# 000_Main.net
KiCad netlist of a schematic drawn in Altium Designer
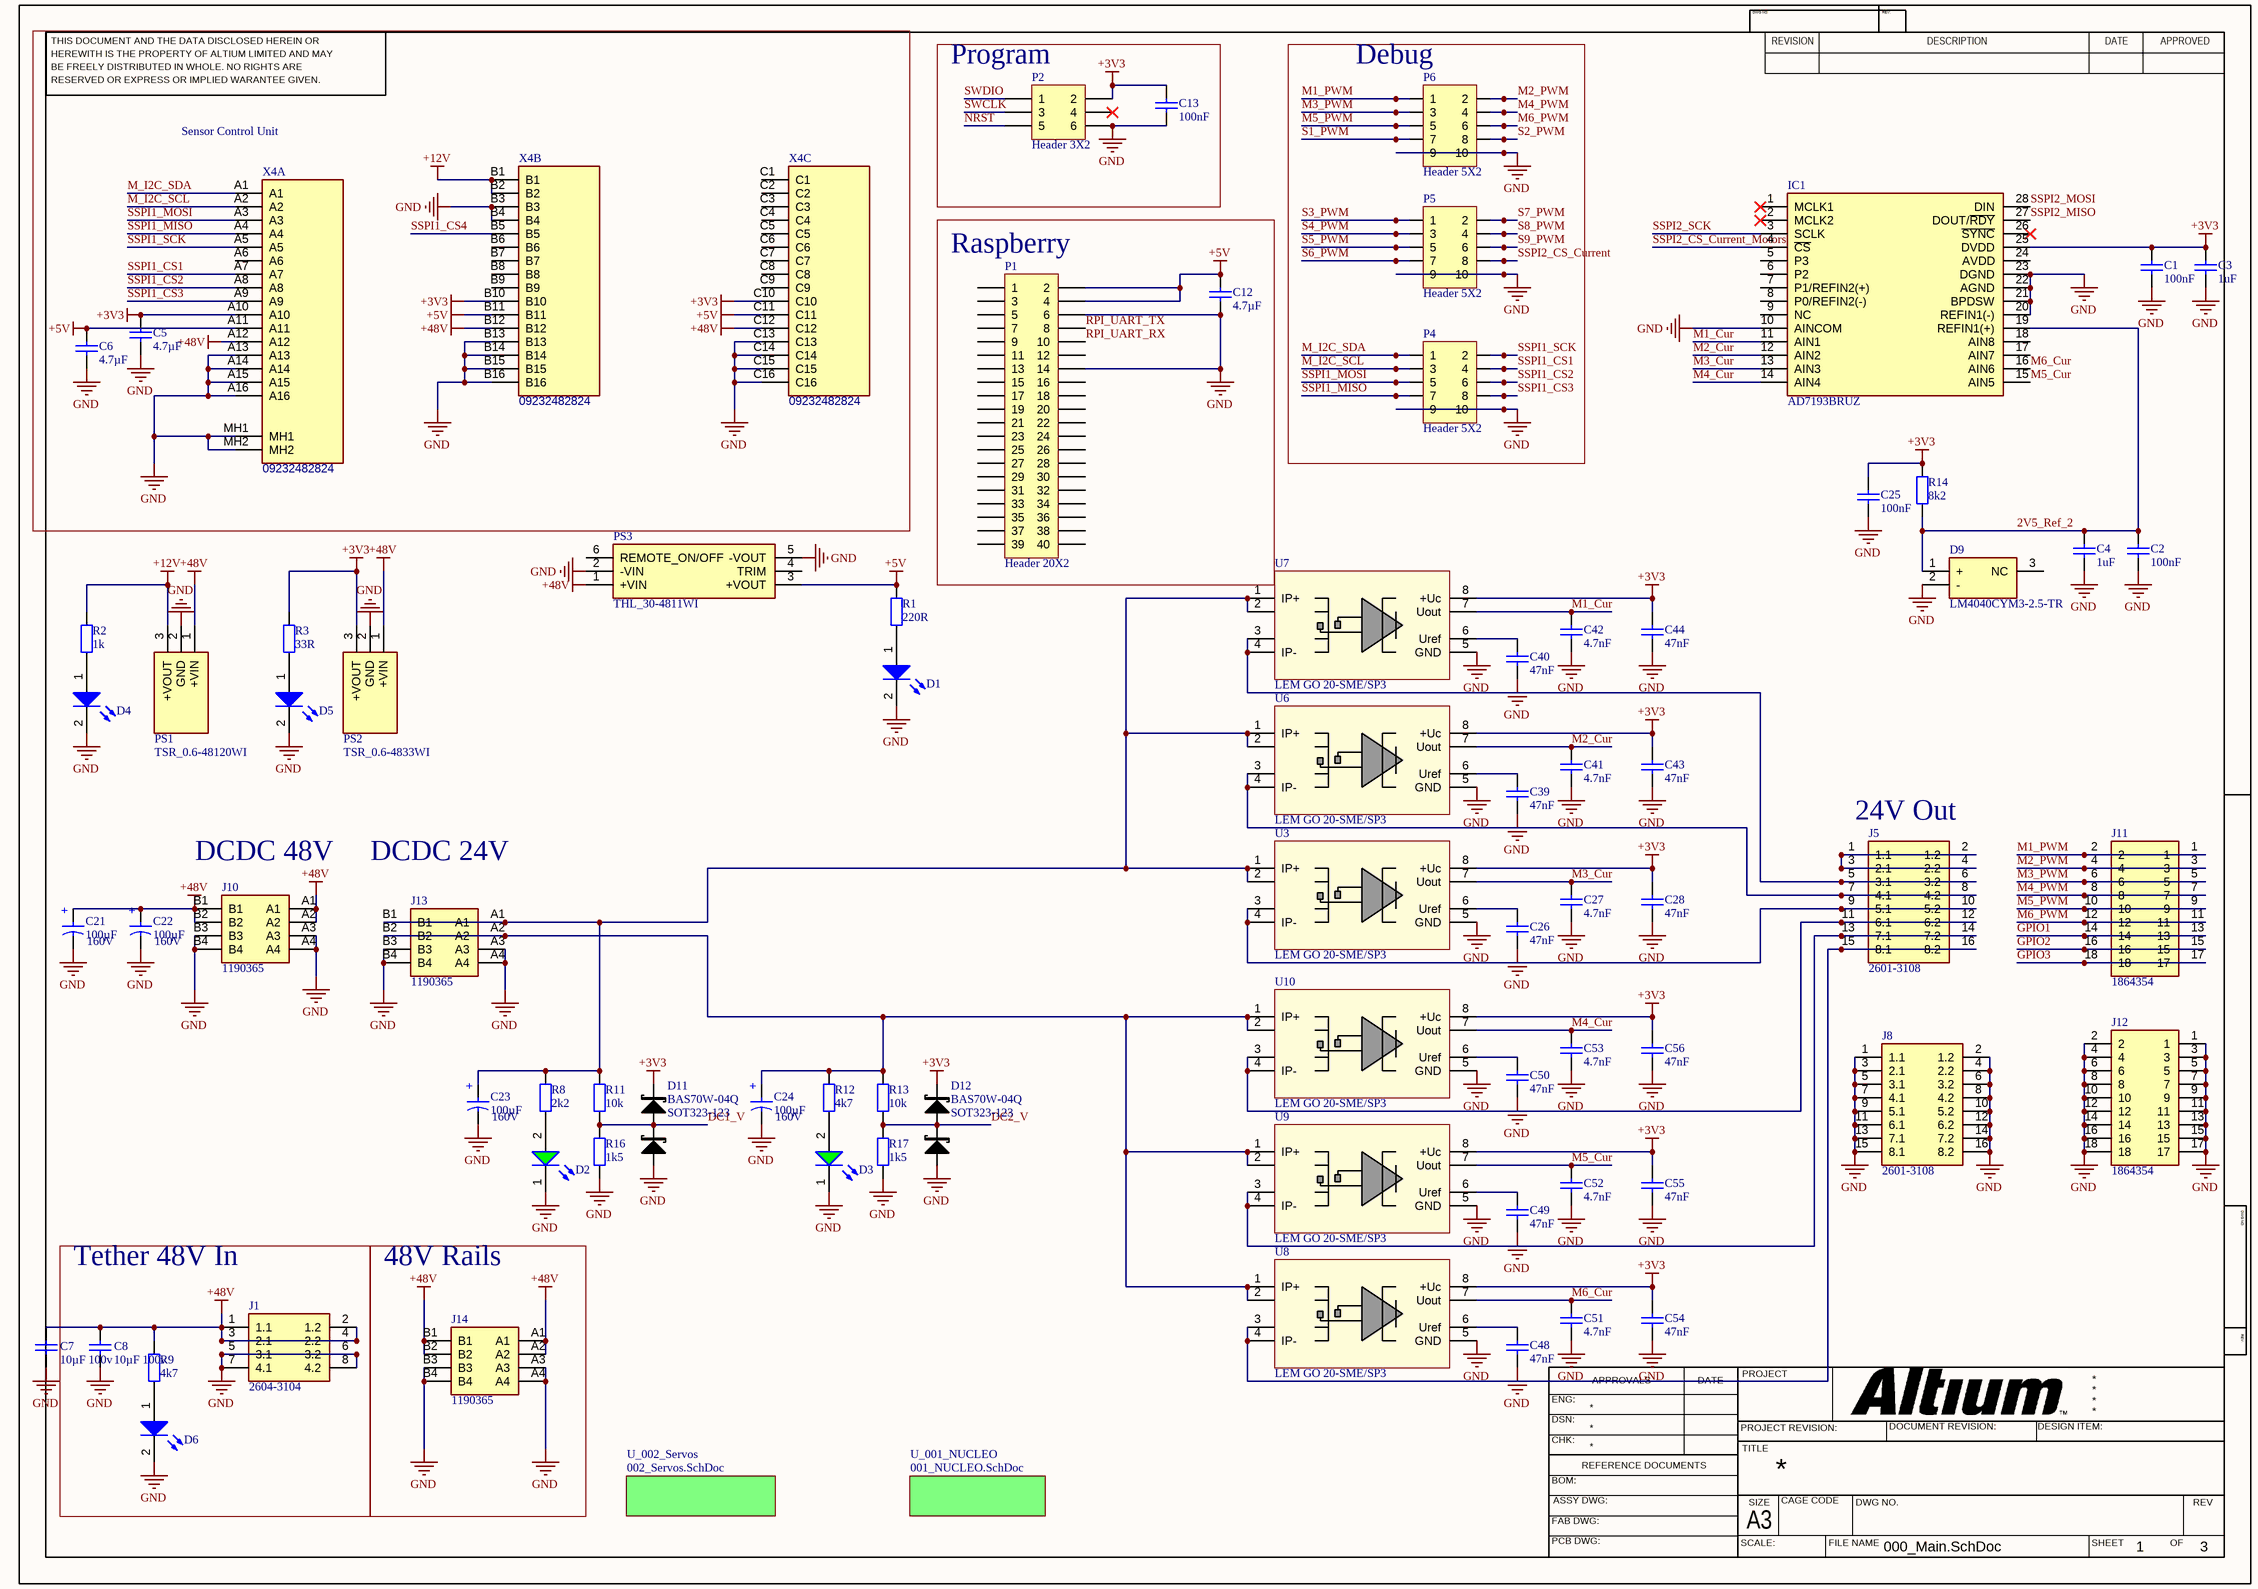
[diagram p0: 000_Main.SchDoc]

(export (version "E")
  (design (tool "Eeschema 10.0.6"))
  (components
    (comp (ref "C1")
      (value "100nF")
      (footprint "Miscellaneous Devices:6-0805_L")
      (description "Capacitor")
      (fields (field (name "PUBLISHER") "Altium Limited"))
      (libsource (lib "Miscellaneous Devices") (part "Cap"))
    )
    (comp (ref "C2")
      (value "100nF")
      (footprint "Miscellaneous Devices:6-0805_L")
      (description "Capacitor")
      (fields (field (name "PUBLISHER") "Altium Limited"))
      (libsource (lib "Miscellaneous Devices") (part "Cap"))
    )
    (comp (ref "C3")
      (value "1uF")
      (footprint "Miscellaneous Devices:6-0805_L")
      (description "Capacitor")
      (fields (field (name "PUBLISHER") "Altium Limited"))
      (libsource (lib "Miscellaneous Devices") (part "Cap"))
    )
    (comp (ref "C4")
      (value "1uF")
      (footprint "Miscellaneous Devices:6-0805_L")
      (description "Capacitor")
      (fields (field (name "PUBLISHER") "Altium Limited"))
      (libsource (lib "Miscellaneous Devices") (part "Cap"))
    )
    (comp (ref "C5")
      (value "4.7µF")
      (footprint "WCAP-CSGP_1210_L3.2W2.5H2.5")
      (description "WCAP-CSGP Multilayer Ceramic Chip Capacitor, General Purpose, size 1210, X7R, 4.7µF, 50VDC")
      (fields
        (field (name "MANUFACTURER PART NUMBER") "885012209048")
        (field (name "MANUFACTURER") "Wurth Elektronik")
      )
      (libsource (lib "Altium_WCAP-CSGP (rev22f)") (part "885012209048"))
    )
    (comp (ref "C6")
      (value "4.7µF")
      (footprint "WCAP-CSGP_1210_L3.2W2.5H2.5")
      (description "WCAP-CSGP Multilayer Ceramic Chip Capacitor, General Purpose, size 1210, X7R, 4.7µF, 50VDC")
      (fields
        (field (name "MANUFACTURER PART NUMBER") "885012209048")
        (field (name "MANUFACTURER") "Wurth Elektronik")
      )
      (libsource (lib "Altium_WCAP-CSGP (rev22f)") (part "885012209048"))
    )
    (comp (ref "C7")
      (value "10µF 100v")
      (footprint "WCAP-CSGP_2220_L5.7W5H2.8")
      (fields
        (field (name "MANUFACTURER PART NUMBER") "885012214006")
        (field (name "MANUFACTURER") "Wurth Elektronik")
      )
      (libsource (lib "Altium_WCAP-CSGP (rev22f)") (part "885012214006"))
    )
    (comp (ref "C8")
      (value "10µF 100v")
      (footprint "WCAP-CSGP_2220_L5.7W5H2.8")
      (fields
        (field (name "MANUFACTURER PART NUMBER") "885012214006")
        (field (name "MANUFACTURER") "Wurth Elektronik")
      )
      (libsource (lib "Altium_WCAP-CSGP (rev22f)") (part "885012214006"))
    )
    (comp (ref "C12")
      (value "4.7µF")
      (footprint "WCAP-CSGP_1210_L3.2W2.5H2.5")
      (description "WCAP-CSGP Multilayer Ceramic Chip Capacitor, General Purpose, size 1210, X7R, 4.7µF, 50VDC")
      (fields
        (field (name "MANUFACTURER PART NUMBER") "885012209048")
        (field (name "MANUFACTURER") "Wurth Elektronik")
      )
      (libsource (lib "Altium_WCAP-CSGP (rev22f)") (part "885012209048"))
    )
    (comp (ref "C13")
      (value "100nF")
      (footprint "WCAP-CSGP_0805_L2W1.25H0.8_Reflow")
      (description "WCAP-CSGP Multilayer Ceramic Chip Capacitor, General Purpose, size 0805, X7R, 100nF, 50VDC")
      (fields
        (field (name "MANUFACTURER PART NUMBER") "885012207098R")
        (field (name "MANUFACTURER") "Wurth Elektronik")
      )
      (libsource (lib "Altium_WCAP-CSGP (rev22f)") (part "885012207098R"))
    )
    (comp (ref "C21")
      (value "100µF")
      (footprint "WCAP-AT1H_D18H21")
      (description "WCAP-AT1H Aluminum Electrolytic Capacitor, Radial, THT, D18 x H21mm, 100µF, 160V")
      (fields
        (field (name "MANUFACTURER PART NUMBER") "860240981006")
        (field (name "MANUFACTURER") "Wurth Elektronik")
        (field (name "CAPACITANCE") "100µF")
        (field (name "RATED VOLTAGE (DC)") "160V")
      )
      (libsource (lib "Altium_WCAP-AT1H (rev22c)") (part "860240981006"))
    )
    (comp (ref "C22")
      (value "100µF")
      (footprint "WCAP-AT1H_D18H21")
      (description "WCAP-AT1H Aluminum Electrolytic Capacitor, Radial, THT, D18 x H21mm, 100µF, 160V")
      (fields
        (field (name "MANUFACTURER PART NUMBER") "860240981006")
        (field (name "MANUFACTURER") "Wurth Elektronik")
        (field (name "CAPACITANCE") "100µF")
        (field (name "RATED VOLTAGE (DC)") "160V")
      )
      (libsource (lib "Altium_WCAP-AT1H (rev22c)") (part "860240981006"))
    )
    (comp (ref "C23")
      (value "100µF")
      (footprint "WCAP-AT1H_D18H21")
      (description "WCAP-AT1H Aluminum Electrolytic Capacitor, Radial, THT, D18 x H21mm, 100µF, 160V")
      (fields
        (field (name "MANUFACTURER PART NUMBER") "860240981006")
        (field (name "MANUFACTURER") "Wurth Elektronik")
        (field (name "CAPACITANCE") "100µF")
        (field (name "RATED VOLTAGE (DC)") "160V")
      )
      (libsource (lib "Altium_WCAP-AT1H (rev22c)") (part "860240981006"))
    )
    (comp (ref "C24")
      (value "100µF")
      (footprint "WCAP-AT1H_D18H21")
      (description "WCAP-AT1H Aluminum Electrolytic Capacitor, Radial, THT, D18 x H21mm, 100µF, 160V")
      (fields
        (field (name "MANUFACTURER PART NUMBER") "860240981006")
        (field (name "MANUFACTURER") "Wurth Elektronik")
        (field (name "CAPACITANCE") "100µF")
        (field (name "RATED VOLTAGE (DC)") "160V")
      )
      (libsource (lib "Altium_WCAP-AT1H (rev22c)") (part "860240981006"))
    )
    (comp (ref "C25")
      (value "100nF")
      (footprint "Miscellaneous Devices:6-0805_L")
      (description "Capacitor")
      (fields (field (name "PUBLISHER") "Altium Limited"))
      (libsource (lib "Miscellaneous Devices") (part "Cap"))
    )
    (comp (ref "C26")
      (value "47nF")
      (footprint "WCAP-CSGP_0805_L2W1.25H0.8_Reflow")
      (description "WCAP-CSGP Multilayer Ceramic Chip Capacitor, General Purpose, size 0805, X7R, 47nF, 50VDC")
      (fields
        (field (name "MANUFACTURER PART NUMBER") "885012207096")
        (field (name "MANUFACTURER") "Wurth Elektronik")
        (field (name "CAPACITANCE") "47nF")
      )
      (libsource (lib "Altium_WCAP-CSGP (rev22f)") (part "885012207096"))
    )
    (comp (ref "C27")
      (value "4.7nF")
      (footprint "WCAP-CSGP_0805_L2W1.25H0.8_Reflow")
      (description "WCAP-CSGP Multilayer Ceramic Chip Capacitor, General Purpose, size 0805, X7R, 4.7nF, 50VDC")
      (fields
        (field (name "MANUFACTURER PART NUMBER") "885012207090")
        (field (name "MANUFACTURER") "Wurth Elektronik")
        (field (name "CAPACITANCE") "4.7nF")
      )
      (libsource (lib "Altium_WCAP-CSGP (rev22f)") (part "885012207090"))
    )
    (comp (ref "C28")
      (value "47nF")
      (footprint "WCAP-CSGP_0805_L2W1.25H0.8_Reflow")
      (description "WCAP-CSGP Multilayer Ceramic Chip Capacitor, General Purpose, size 0805, X7R, 47nF, 50VDC")
      (fields
        (field (name "MANUFACTURER PART NUMBER") "885012207096")
        (field (name "MANUFACTURER") "Wurth Elektronik")
        (field (name "CAPACITANCE") "47nF")
      )
      (libsource (lib "Altium_WCAP-CSGP (rev22f)") (part "885012207096"))
    )
    (comp (ref "C39")
      (value "47nF")
      (footprint "WCAP-CSGP_0805_L2W1.25H0.8_Reflow")
      (description "WCAP-CSGP Multilayer Ceramic Chip Capacitor, General Purpose, size 0805, X7R, 47nF, 50VDC")
      (fields
        (field (name "MANUFACTURER PART NUMBER") "885012207096")
        (field (name "MANUFACTURER") "Wurth Elektronik")
        (field (name "CAPACITANCE") "47nF")
      )
      (libsource (lib "Altium_WCAP-CSGP (rev22f)") (part "885012207096"))
    )
    (comp (ref "C40")
      (value "47nF")
      (footprint "WCAP-CSGP_0805_L2W1.25H0.8_Reflow")
      (description "WCAP-CSGP Multilayer Ceramic Chip Capacitor, General Purpose, size 0805, X7R, 47nF, 50VDC")
      (fields
        (field (name "MANUFACTURER PART NUMBER") "885012207096")
        (field (name "MANUFACTURER") "Wurth Elektronik")
        (field (name "CAPACITANCE") "47nF")
      )
      (libsource (lib "Altium_WCAP-CSGP (rev22f)") (part "885012207096"))
    )
    (comp (ref "C41")
      (value "4.7nF")
      (footprint "WCAP-CSGP_0805_L2W1.25H0.8_Reflow")
      (description "WCAP-CSGP Multilayer Ceramic Chip Capacitor, General Purpose, size 0805, X7R, 4.7nF, 50VDC")
      (fields
        (field (name "MANUFACTURER PART NUMBER") "885012207090")
        (field (name "MANUFACTURER") "Wurth Elektronik")
        (field (name "CAPACITANCE") "4.7nF")
      )
      (libsource (lib "Altium_WCAP-CSGP (rev22f)") (part "885012207090"))
    )
    (comp (ref "C42")
      (value "4.7nF")
      (footprint "WCAP-CSGP_0805_L2W1.25H0.8_Reflow")
      (description "WCAP-CSGP Multilayer Ceramic Chip Capacitor, General Purpose, size 0805, X7R, 4.7nF, 50VDC")
      (fields
        (field (name "MANUFACTURER PART NUMBER") "885012207090")
        (field (name "MANUFACTURER") "Wurth Elektronik")
        (field (name "CAPACITANCE") "4.7nF")
      )
      (libsource (lib "Altium_WCAP-CSGP (rev22f)") (part "885012207090"))
    )
    (comp (ref "C43")
      (value "47nF")
      (footprint "WCAP-CSGP_0805_L2W1.25H0.8_Reflow")
      (description "WCAP-CSGP Multilayer Ceramic Chip Capacitor, General Purpose, size 0805, X7R, 47nF, 50VDC")
      (fields
        (field (name "MANUFACTURER PART NUMBER") "885012207096")
        (field (name "MANUFACTURER") "Wurth Elektronik")
        (field (name "CAPACITANCE") "47nF")
      )
      (libsource (lib "Altium_WCAP-CSGP (rev22f)") (part "885012207096"))
    )
    (comp (ref "C44")
      (value "47nF")
      (footprint "WCAP-CSGP_0805_L2W1.25H0.8_Reflow")
      (description "WCAP-CSGP Multilayer Ceramic Chip Capacitor, General Purpose, size 0805, X7R, 47nF, 50VDC")
      (fields
        (field (name "MANUFACTURER PART NUMBER") "885012207096")
        (field (name "MANUFACTURER") "Wurth Elektronik")
        (field (name "CAPACITANCE") "47nF")
      )
      (libsource (lib "Altium_WCAP-CSGP (rev22f)") (part "885012207096"))
    )
    (comp (ref "C48")
      (value "47nF")
      (footprint "WCAP-CSGP_0805_L2W1.25H0.8_Reflow")
      (description "WCAP-CSGP Multilayer Ceramic Chip Capacitor, General Purpose, size 0805, X7R, 47nF, 50VDC")
      (fields
        (field (name "MANUFACTURER PART NUMBER") "885012207096")
        (field (name "MANUFACTURER") "Wurth Elektronik")
        (field (name "CAPACITANCE") "47nF")
      )
      (libsource (lib "Altium_WCAP-CSGP (rev22f)") (part "885012207096"))
    )
    (comp (ref "C49")
      (value "47nF")
      (footprint "WCAP-CSGP_0805_L2W1.25H0.8_Reflow")
      (description "WCAP-CSGP Multilayer Ceramic Chip Capacitor, General Purpose, size 0805, X7R, 47nF, 50VDC")
      (fields
        (field (name "MANUFACTURER PART NUMBER") "885012207096")
        (field (name "MANUFACTURER") "Wurth Elektronik")
        (field (name "CAPACITANCE") "47nF")
      )
      (libsource (lib "Altium_WCAP-CSGP (rev22f)") (part "885012207096"))
    )
    (comp (ref "C50")
      (value "47nF")
      (footprint "WCAP-CSGP_0805_L2W1.25H0.8_Reflow")
      (description "WCAP-CSGP Multilayer Ceramic Chip Capacitor, General Purpose, size 0805, X7R, 47nF, 50VDC")
      (fields
        (field (name "MANUFACTURER PART NUMBER") "885012207096")
        (field (name "MANUFACTURER") "Wurth Elektronik")
        (field (name "CAPACITANCE") "47nF")
      )
      (libsource (lib "Altium_WCAP-CSGP (rev22f)") (part "885012207096"))
    )
    (comp (ref "C51")
      (value "4.7nF")
      (footprint "WCAP-CSGP_0805_L2W1.25H0.8_Reflow")
      (description "WCAP-CSGP Multilayer Ceramic Chip Capacitor, General Purpose, size 0805, X7R, 4.7nF, 50VDC")
      (fields
        (field (name "MANUFACTURER PART NUMBER") "885012207090")
        (field (name "MANUFACTURER") "Wurth Elektronik")
        (field (name "CAPACITANCE") "4.7nF")
      )
      (libsource (lib "Altium_WCAP-CSGP (rev22f)") (part "885012207090"))
    )
    (comp (ref "C52")
      (value "4.7nF")
      (footprint "WCAP-CSGP_0805_L2W1.25H0.8_Reflow")
      (description "WCAP-CSGP Multilayer Ceramic Chip Capacitor, General Purpose, size 0805, X7R, 4.7nF, 50VDC")
      (fields
        (field (name "MANUFACTURER PART NUMBER") "885012207090")
        (field (name "MANUFACTURER") "Wurth Elektronik")
        (field (name "CAPACITANCE") "4.7nF")
      )
      (libsource (lib "Altium_WCAP-CSGP (rev22f)") (part "885012207090"))
    )
    (comp (ref "C53")
      (value "4.7nF")
      (footprint "WCAP-CSGP_0805_L2W1.25H0.8_Reflow")
      (description "WCAP-CSGP Multilayer Ceramic Chip Capacitor, General Purpose, size 0805, X7R, 4.7nF, 50VDC")
      (fields
        (field (name "MANUFACTURER PART NUMBER") "885012207090")
        (field (name "MANUFACTURER") "Wurth Elektronik")
        (field (name "CAPACITANCE") "4.7nF")
      )
      (libsource (lib "Altium_WCAP-CSGP (rev22f)") (part "885012207090"))
    )
    (comp (ref "C54")
      (value "47nF")
      (footprint "WCAP-CSGP_0805_L2W1.25H0.8_Reflow")
      (description "WCAP-CSGP Multilayer Ceramic Chip Capacitor, General Purpose, size 0805, X7R, 47nF, 50VDC")
      (fields
        (field (name "MANUFACTURER PART NUMBER") "885012207096")
        (field (name "MANUFACTURER") "Wurth Elektronik")
        (field (name "CAPACITANCE") "47nF")
      )
      (libsource (lib "Altium_WCAP-CSGP (rev22f)") (part "885012207096"))
    )
    (comp (ref "C55")
      (value "47nF")
      (footprint "WCAP-CSGP_0805_L2W1.25H0.8_Reflow")
      (description "WCAP-CSGP Multilayer Ceramic Chip Capacitor, General Purpose, size 0805, X7R, 47nF, 50VDC")
      (fields
        (field (name "MANUFACTURER PART NUMBER") "885012207096")
        (field (name "MANUFACTURER") "Wurth Elektronik")
        (field (name "CAPACITANCE") "47nF")
      )
      (libsource (lib "Altium_WCAP-CSGP (rev22f)") (part "885012207096"))
    )
    (comp (ref "C56")
      (value "47nF")
      (footprint "WCAP-CSGP_0805_L2W1.25H0.8_Reflow")
      (description "WCAP-CSGP Multilayer Ceramic Chip Capacitor, General Purpose, size 0805, X7R, 47nF, 50VDC")
      (fields
        (field (name "MANUFACTURER PART NUMBER") "885012207096")
        (field (name "MANUFACTURER") "Wurth Elektronik")
        (field (name "CAPACITANCE") "47nF")
      )
      (libsource (lib "Altium_WCAP-CSGP (rev22f)") (part "885012207096"))
    )
    (comp (ref "D1")
      (value "Blue, 3.2V, 140°")
      (footprint "WL-SMCW_0603_150060xx75003")
      (description "WL-SMCW Mono-color Chip LED Waterclear, size 0603, Blue, 3.2V, 140°")
      (fields
        (field (name "MANUFACTURER PART NUMBER") "150060BS75003")
        (field (name "MANUFACTURER") "Wurth Elektronik")
      )
      (libsource (lib "Altium_WL-SMCW (rev22d)") (part "150060BS75003"))
    )
    (comp (ref "D2")
      (value "Green, 3.3V, 40°")
      (footprint "WL-SMCW_0603_150060xx8x000")
      (description "WL-SMCW Mono-color Chip LED Waterclear, size 0603, Green, 3.3V, 40°")
      (fields
        (field (name "MANUFACTURER PART NUMBER") "150060GS84000")
        (field (name "MANUFACTURER") "Wurth Elektronik")
      )
      (libsource (lib "Altium_WL-SMCW (rev22d)") (part "150060GS84000"))
    )
    (comp (ref "D3")
      (value "Green, 3.3V, 40°")
      (footprint "WL-SMCW_0603_150060xx8x000")
      (description "WL-SMCW Mono-color Chip LED Waterclear, size 0603, Green, 3.3V, 40°")
      (fields
        (field (name "MANUFACTURER PART NUMBER") "150060GS84000")
        (field (name "MANUFACTURER") "Wurth Elektronik")
      )
      (libsource (lib "Altium_WL-SMCW (rev22d)") (part "150060GS84000"))
    )
    (comp (ref "D4")
      (value "Blue, 3.2V, 140°")
      (footprint "WL-SMCW_0603_150060xx75003")
      (description "WL-SMCW Mono-color Chip LED Waterclear, size 0603, Blue, 3.2V, 140°")
      (fields
        (field (name "MANUFACTURER PART NUMBER") "150060BS75003")
        (field (name "MANUFACTURER") "Wurth Elektronik")
      )
      (libsource (lib "Altium_WL-SMCW (rev22d)") (part "150060BS75003"))
    )
    (comp (ref "D5")
      (value "Blue, 3.2V, 140°")
      (footprint "WL-SMCW_0603_150060xx75003")
      (description "WL-SMCW Mono-color Chip LED Waterclear, size 0603, Blue, 3.2V, 140°")
      (fields
        (field (name "MANUFACTURER PART NUMBER") "150060BS75003")
        (field (name "MANUFACTURER") "Wurth Elektronik")
      )
      (libsource (lib "Altium_WL-SMCW (rev22d)") (part "150060BS75003"))
    )
    (comp (ref "D6")
      (value "Blue, 3.2V, 140°")
      (footprint "WL-SMCW_0603_150060xx75003")
      (description "WL-SMCW Mono-color Chip LED Waterclear, size 0603, Blue, 3.2V, 140°")
      (fields
        (field (name "MANUFACTURER PART NUMBER") "150060BS75003")
        (field (name "MANUFACTURER") "Wurth Elektronik")
      )
      (libsource (lib "Altium_WL-SMCW (rev22d)") (part "150060BS75003"))
    )
    (comp (ref "D9")
      (value "LM4040CYM3-2.5-TR")
      (footprint "E-Stall_lib:SOT - 23")
      (description "Integrated Circuit")
      (fields (field (name "MOUSER PART NUMBER") "998-LM4040CYM3-2.5TR"))
      (libsource (lib "SamacSys") (part "LM4040CYM3-2.5-TR"))
    )
    (comp (ref "D11")
      (value "BAS70W-04Q")
      (footprint "E-Stall_lib:SOT323-123")
      (description "DUAL SCHOTTKY DIODE SERIES")
      (libsource (lib "E-Stall_lib") (part "Dual Schottky Diode"))
    )
    (comp (ref "D12")
      (value "BAS70W-04Q")
      (footprint "E-Stall_lib:SOT323-123")
      (description "DUAL SCHOTTKY DIODE SERIES")
      (libsource (lib "E-Stall_lib") (part "Dual Schottky Diode"))
    )
    (comp (ref "IC1")
      (value "AD7193BRUZ")
      (footprint "SamacSys:SOP65P640X120-28N")
      (description "Integrated Circuit")
      (fields (field (name "MOUSER PART NUMBER") "584-AD7193BRUZ"))
      (libsource (lib "*") (part "AD7193BRUZ"))
    )
    (comp (ref "J1")
      (value "2604-3104")
      (footprint "26043104")
      (description "PCB terminal block; lever; 4 mm; Pin spacing 5 mm; 4-pole; Push-in CAGE CLAMP")
      (libsource (lib "2604-3104") (part "2604-3104"))
    )
    (comp (ref "J5")
      (value "2601-3108")
      (footprint "SamacSys:26013108")
      (description "Connector")
      (libsource (lib "*") (part "2601-3108"))
    )
    (comp (ref "J8")
      (value "2601-3108")
      (footprint "SamacSys:26013108")
      (description "Connector")
      (libsource (lib "*") (part "2601-3108"))
    )
    (comp (ref "J10")
      (value "1190365")
      (footprint "1190365")
      (description "Fixed Terminal Blocks LPTA 2,5/ 4-5,0")
      (fields (field (name "MOUSER PART NUMBER") "651-1190365"))
      (libsource (lib "1190365") (part "1190365"))
    )
    (comp (ref "J11")
      (value "1864354")
      (footprint "1864354")
      (description "Conn Terminal Block 9 POS 3.5mm Spring Clamp Thru-Hole 13.5A")
      (fields (field (name "MOUSER PART NUMBER") "651-1864354"))
      (libsource (lib "1864354") (part "1864354"))
    )
    (comp (ref "J12")
      (value "1864354")
      (footprint "1864354")
      (description "Conn Terminal Block 9 POS 3.5mm Spring Clamp Thru-Hole 13.5A")
      (fields (field (name "MOUSER PART NUMBER") "651-1864354"))
      (libsource (lib "1864354") (part "1864354"))
    )
    (comp (ref "J13")
      (value "1190365")
      (footprint "1190365")
      (description "Fixed Terminal Blocks LPTA 2,5/ 4-5,0")
      (fields (field (name "MOUSER PART NUMBER") "651-1190365"))
      (libsource (lib "1190365") (part "1190365"))
    )
    (comp (ref "J14")
      (value "1190365")
      (footprint "1190365")
      (description "Fixed Terminal Blocks LPTA 2,5/ 4-5,0")
      (fields (field (name "MOUSER PART NUMBER") "651-1190365"))
      (libsource (lib "1190365") (part "1190365"))
    )
    (comp (ref "P1")
      (value "Header 20X2")
      (footprint "HDR2X20")
      (description "Header, 20-Pin, Dual row")
      (fields (field (name "PUBLISHER") "Altium Limited"))
      (libsource (lib "Miscellaneous Connectors") (part "Header 20X2"))
    )
    (comp (ref "P2")
      (value "Header 3X2")
      (footprint "HDR2X3")
      (description "Header, 3-Pin, Dual row")
      (fields (field (name "PUBLISHER") "Altium Limited"))
      (libsource (lib "Miscellaneous Connectors") (part "Header 3X2"))
    )
    (comp (ref "P4")
      (value "Header 5X2")
      (footprint "HDR2X5")
      (description "Header, 5-Pin, Dual row")
      (fields (field (name "PUBLISHER") "Altium Limited"))
      (libsource (lib "Miscellaneous Connectors") (part "Header 5X2"))
    )
    (comp (ref "P5")
      (value "Header 5X2")
      (footprint "HDR2X5")
      (description "Header, 5-Pin, Dual row")
      (fields (field (name "PUBLISHER") "Altium Limited"))
      (libsource (lib "Miscellaneous Connectors") (part "Header 5X2"))
    )
    (comp (ref "P6")
      (value "Header 5X2")
      (footprint "HDR2X5")
      (description "Header, 5-Pin, Dual row")
      (fields (field (name "PUBLISHER") "Altium Limited"))
      (libsource (lib "Miscellaneous Connectors") (part "Header 5X2"))
    )
    (comp (ref "PS1")
      (value "TSR_0.6-48120WI")
      (footprint "SamacSys:TSR0648120WI")
      (description "Power Supply")
      (fields
        (field (name "MANUFACTURER_PART_NUMBER") "TSR 0.6-48120WI")
        (field (name "MOUSER PART NUMBER") "495-TSR0.6-48120WI")
      )
      (libsource (lib "*") (part "TSR_0.6-48120WI"))
    )
    (comp (ref "PS2")
      (value "TSR_0.6-4833WI")
      (footprint "SamacSys:TSR0648120WI")
      (description "Power Supply")
      (fields
        (field (name "MANUFACTURER_PART_NUMBER") "TSR 0.6-4833WI")
        (field (name "MOUSER PART NUMBER") "495-TSR0.6-4833WI")
      )
      (libsource (lib "*") (part "TSR_0.6-4833WI"))
    )
    (comp (ref "PS3")
      (value "THL_30-4811WI")
      (footprint "SamacSys:THL304811WI")
      (description "Power Supply")
      (fields
        (field (name "MANUFACTURER_PART_NUMBER") "THL 30-4811WI")
        (field (name "MOUSER PART NUMBER") "495-THL30-4811WI")
      )
      (libsource (lib "*") (part "THL_30-4811WI"))
    )
    (comp (ref "R1")
      (value "220R")
      (footprint "Miscellaneous Devices:6-0805_M")
      (description "Resistor")
      (fields (field (name "PUBLISHER") "Altium Limited"))
      (libsource (lib "Miscellaneous Devices") (part "Res2"))
    )
    (comp (ref "R2")
      (value "1k")
      (footprint "Miscellaneous Devices:6-0805_M")
      (description "Resistor")
      (fields (field (name "PUBLISHER") "Altium Limited"))
      (libsource (lib "Miscellaneous Devices") (part "Res2"))
    )
    (comp (ref "R3")
      (value "33R")
      (footprint "Miscellaneous Devices:6-0805_M")
      (description "Resistor")
      (fields (field (name "PUBLISHER") "Altium Limited"))
      (libsource (lib "Miscellaneous Devices") (part "Res2"))
    )
    (comp (ref "R8")
      (value "2k2")
      (footprint "Miscellaneous Devices:6-0805_M")
      (description "Resistor")
      (fields (field (name "PUBLISHER") "Altium Limited"))
      (libsource (lib "Miscellaneous Devices") (part "Res2"))
    )
    (comp (ref "R9")
      (value "4k7")
      (footprint "Miscellaneous Devices:6-0805_M")
      (description "Resistor")
      (fields (field (name "PUBLISHER") "Altium Limited"))
      (libsource (lib "Miscellaneous Devices") (part "Res2"))
    )
    (comp (ref "R11")
      (value "10k")
      (footprint "Miscellaneous Devices:6-0805_M")
      (description "Resistor")
      (fields (field (name "PUBLISHER") "Altium Limited"))
      (libsource (lib "Miscellaneous Devices") (part "Res2"))
    )
    (comp (ref "R12")
      (value "4k7")
      (footprint "Miscellaneous Devices:6-0805_M")
      (description "Resistor")
      (fields (field (name "PUBLISHER") "Altium Limited"))
      (libsource (lib "Miscellaneous Devices") (part "Res2"))
    )
    (comp (ref "R13")
      (value "10k")
      (footprint "Miscellaneous Devices:6-0805_M")
      (description "Resistor")
      (fields (field (name "PUBLISHER") "Altium Limited"))
      (libsource (lib "Miscellaneous Devices") (part "Res2"))
    )
    (comp (ref "R14")
      (value "8k2")
      (footprint "Miscellaneous Devices:6-0805_M")
      (description "Resistor")
      (fields (field (name "PUBLISHER") "Altium Limited"))
      (libsource (lib "Miscellaneous Devices") (part "Res2"))
    )
    (comp (ref "R16")
      (value "1k5")
      (footprint "Miscellaneous Devices:6-0805_M")
      (description "Resistor")
      (fields (field (name "PUBLISHER") "Altium Limited"))
      (libsource (lib "Miscellaneous Devices") (part "Res2"))
    )
    (comp (ref "R17")
      (value "1k5")
      (footprint "Miscellaneous Devices:6-0805_M")
      (description "Resistor")
      (fields (field (name "PUBLISHER") "Altium Limited"))
      (libsource (lib "Miscellaneous Devices") (part "Res2"))
    )
    (comp (ref "U3")
      (value "LEM GO 20-SME/SP3")
      (footprint "Lem_sme_SOIC8")
      (description "Integrated Current Transducer GO-SME s")
      (fields (field (name "MANUFACTURER") "LEM"))
      (libsource (lib "LEM_SME") (part "LEM_SME"))
    )
    (comp (ref "U6")
      (value "LEM GO 20-SME/SP3")
      (footprint "Lem_sme_SOIC8")
      (description "Integrated Current Transducer GO-SME s")
      (fields (field (name "MANUFACTURER") "LEM"))
      (libsource (lib "LEM_SME") (part "LEM_SME"))
    )
    (comp (ref "U7")
      (value "LEM GO 20-SME/SP3")
      (footprint "Lem_sme_SOIC8")
      (description "Integrated Current Transducer GO-SME s")
      (fields (field (name "MANUFACTURER") "LEM"))
      (libsource (lib "LEM_SME") (part "LEM_SME"))
    )
    (comp (ref "U8")
      (value "LEM GO 20-SME/SP3")
      (footprint "Lem_sme_SOIC8")
      (description "Integrated Current Transducer GO-SME s")
      (fields (field (name "MANUFACTURER") "LEM"))
      (libsource (lib "LEM_SME") (part "LEM_SME"))
    )
    (comp (ref "U9")
      (value "LEM GO 20-SME/SP3")
      (footprint "Lem_sme_SOIC8")
      (description "Integrated Current Transducer GO-SME s")
      (fields (field (name "MANUFACTURER") "LEM"))
      (libsource (lib "LEM_SME") (part "LEM_SME"))
    )
    (comp (ref "U10")
      (value "LEM GO 20-SME/SP3")
      (footprint "Lem_sme_SOIC8")
      (description "Integrated Current Transducer GO-SME s")
      (fields (field (name "MANUFACTURER") "LEM"))
      (libsource (lib "LEM_SME") (part "LEM_SME"))
    )
    (comp (ref "X4")
      (value "09232482824")
      (footprint "09232482824")
      (description "DIN 2C female straight 48pin, 2.9mm tails, PL1")
      (fields (field (name "MANUFACTURER") "HARTING") (field (name "MOUSER PART NUMBER") "617-09232482824"))
      (libsource (lib "MATE-ROV_LIB") (part "09232482824"))
    )
  )
  (nets
    (net (code "1") (name "+3V3") (class "Default")
      (node (ref "C1") (pin "2") (pinfunction "2_2") (pintype "passive"))
      (node (ref "C13") (pin "1") (pinfunction "1_1") (pintype "passive"))
      (node (ref "C25") (pin "2") (pinfunction "2_2") (pintype "passive"))
      (node (ref "C28") (pin "2") (pinfunction "2_2") (pintype "passive"))
      (node (ref "C3") (pin "2") (pinfunction "2_2") (pintype "passive"))
      (node (ref "C43") (pin "2") (pinfunction "2_2") (pintype "passive"))
      (node (ref "C44") (pin "2") (pinfunction "2_2") (pintype "passive"))
      (node (ref "C5") (pin "2") (pinfunction "2_2") (pintype "passive"))
      (node (ref "C54") (pin "2") (pinfunction "2_2") (pintype "passive"))
      (node (ref "C55") (pin "2") (pinfunction "2_2") (pintype "passive"))
      (node (ref "C56") (pin "2") (pinfunction "2_2") (pintype "passive"))
      (node (ref "D11") (pin "2") (pinfunction "2_2") (pintype "passive"))
      (node (ref "D12") (pin "2") (pinfunction "2_2") (pintype "passive"))
      (node (ref "IC1") (pin "25") (pinfunction "DVDD_25") (pintype "passive"))
      (node (ref "P2") (pin "2") (pinfunction "2_2") (pintype "passive"))
      (node (ref "PS2") (pin "3") (pinfunction "+VOUT_3") (pintype "passive"))
      (node (ref "R14") (pin "2") (pinfunction "2_2") (pintype "passive"))
      (node (ref "R3") (pin "2") (pinfunction "2_2") (pintype "passive"))
      (node (ref "U10") (pin "8") (pinfunction "+Uc_8") (pintype "passive"))
      (node (ref "U3") (pin "8") (pinfunction "+Uc_8") (pintype "passive"))
      (node (ref "U6") (pin "8") (pinfunction "+Uc_8") (pintype "passive"))
      (node (ref "U7") (pin "8") (pinfunction "+Uc_8") (pintype "passive"))
      (node (ref "U8") (pin "8") (pinfunction "+Uc_8") (pintype "passive"))
      (node (ref "U9") (pin "8") (pinfunction "+Uc_8") (pintype "passive"))
      (node (ref "X4") (pin "A10") (pinfunction "A10_A10") (pintype "passive"))
      (node (ref "X4") (pin "B10") (pinfunction "B10_B10") (pintype "passive"))
      (node (ref "X4") (pin "C10") (pinfunction "C10_C10") (pintype "passive"))
    )
    (net (code "2") (name "+5V") (class "Default")
      (node (ref "C12") (pin "2") (pinfunction "2_2") (pintype "passive"))
      (node (ref "C6") (pin "2") (pinfunction "2_2") (pintype "passive"))
      (node (ref "P1") (pin "2") (pinfunction "2_2") (pintype "passive"))
      (node (ref "P1") (pin "4") (pinfunction "4_4") (pintype "passive"))
      (node (ref "PS3") (pin "3") (pinfunction "+VOUT_3") (pintype "passive"))
      (node (ref "R1") (pin "2") (pinfunction "2_2") (pintype "passive"))
      (node (ref "X4") (pin "A11") (pinfunction "A11_A11") (pintype "passive"))
      (node (ref "X4") (pin "B11") (pinfunction "B11_B11") (pintype "passive"))
      (node (ref "X4") (pin "C11") (pinfunction "C11_C11") (pintype "passive"))
    )
    (net (code "3") (name "+12V") (class "Default")
      (node (ref "PS1") (pin "3") (pinfunction "+VOUT_3") (pintype "passive"))
      (node (ref "R2") (pin "2") (pinfunction "2_2") (pintype "passive"))
      (node (ref "X4") (pin "B1") (pinfunction "B1_B1") (pintype "passive"))
      (node (ref "X4") (pin "B2") (pinfunction "B2_B2") (pintype "passive"))
    )
    (net (code "4") (name "+48V") (class "Default")
      (node (ref "C21") (pin "1") (pinfunction "P_1") (pintype "passive"))
      (node (ref "C22") (pin "1") (pinfunction "P_1") (pintype "passive"))
      (node (ref "C7") (pin "2") (pinfunction "2_2") (pintype "passive"))
      (node (ref "C8") (pin "2") (pinfunction "2_2") (pintype "passive"))
      (node (ref "J1") (pin "1") (pinfunction "1.1_1") (pintype "passive"))
      (node (ref "J1") (pin "2") (pinfunction "1.2_2") (pintype "passive"))
      (node (ref "J1") (pin "3") (pinfunction "2.1_3") (pintype "passive"))
      (node (ref "J1") (pin "4") (pinfunction "2.2_4") (pintype "passive"))
      (node (ref "J10") (pin "A1") (pinfunction "A1_A1") (pintype "passive"))
      (node (ref "J10") (pin "A2") (pinfunction "A2_A2") (pintype "passive"))
      (node (ref "J10") (pin "B1") (pinfunction "B1_B1") (pintype "passive"))
      (node (ref "J10") (pin "B2") (pinfunction "B2_B2") (pintype "passive"))
      (node (ref "J14") (pin "A1") (pinfunction "A1_A1") (pintype "passive"))
      (node (ref "J14") (pin "A2") (pinfunction "A2_A2") (pintype "passive"))
      (node (ref "J14") (pin "B1") (pinfunction "B1_B1") (pintype "passive"))
      (node (ref "J14") (pin "B2") (pinfunction "B2_B2") (pintype "passive"))
      (node (ref "PS1") (pin "1") (pinfunction "+VIN_1") (pintype "passive"))
      (node (ref "PS2") (pin "1") (pinfunction "+VIN_1") (pintype "passive"))
      (node (ref "PS3") (pin "1") (pinfunction "+VIN_1") (pintype "passive"))
      (node (ref "R9") (pin "2") (pinfunction "2_2") (pintype "passive"))
      (node (ref "X4") (pin "A12") (pinfunction "A12_A12") (pintype "passive"))
      (node (ref "X4") (pin "B12") (pinfunction "B12_B12") (pintype "passive"))
      (node (ref "X4") (pin "C12") (pinfunction "C12_C12") (pintype "passive"))
    )
    (net (code "5") (name "/2V5_Ref_2") (class "Default")
      (node (ref "C2") (pin "2") (pinfunction "2_2") (pintype "passive"))
      (node (ref "C4") (pin "2") (pinfunction "2_2") (pintype "passive"))
      (node (ref "D9") (pin "1") (pinfunction "+_1") (pintype "passive"))
      (node (ref "IC1") (pin "19") (pinfunction "REFIN1(+)_19") (pintype "passive"))
      (node (ref "R14") (pin "1") (pinfunction "1_1") (pintype "passive"))
    )
    (net (code "6") (name "/DC1_V") (class "Default")
      (node (ref "D11") (pin "3") (pinfunction "3_3") (pintype "passive"))
      (node (ref "R11") (pin "1") (pinfunction "1_1") (pintype "passive"))
      (node (ref "R16") (pin "2") (pinfunction "2_2") (pintype "passive"))
    )
    (net (code "7") (name "/DC2_V") (class "Default")
      (node (ref "D12") (pin "3") (pinfunction "3_3") (pintype "passive"))
      (node (ref "R13") (pin "1") (pinfunction "1_1") (pintype "passive"))
      (node (ref "R17") (pin "2") (pinfunction "2_2") (pintype "passive"))
    )
    (net (code "8") (name "/GPIO1") (class "Default")
      (node (ref "J11") (pin "13") (pinfunction "13_13") (pintype "passive"))
      (node (ref "J11") (pin "14") (pinfunction "14_14") (pintype "passive"))
    )
    (net (code "9") (name "/GPIO2") (class "Default")
      (node (ref "J11") (pin "15") (pinfunction "15_15") (pintype "passive"))
      (node (ref "J11") (pin "16") (pinfunction "16_16") (pintype "passive"))
    )
    (net (code "10") (name "/GPIO3") (class "Default")
      (node (ref "J11") (pin "17") (pinfunction "17_17") (pintype "passive"))
      (node (ref "J11") (pin "18") (pinfunction "18_18") (pintype "passive"))
    )
    (net (code "11") (name "/M1_Cur") (class "Default")
      (node (ref "C42") (pin "2") (pinfunction "2_2") (pintype "passive"))
      (node (ref "IC1") (pin "11") (pinfunction "AIN1_11") (pintype "passive"))
      (node (ref "U7") (pin "7") (pinfunction "Uout_7") (pintype "passive"))
    )
    (net (code "12") (name "/M1_PWM") (class "Default")
      (node (ref "J11") (pin "1") (pinfunction "1_1") (pintype "passive"))
      (node (ref "J11") (pin "2") (pinfunction "2_2") (pintype "passive"))
      (node (ref "P6") (pin "1") (pinfunction "1_1") (pintype "passive"))
    )
    (net (code "13") (name "/M2_Cur") (class "Default")
      (node (ref "C41") (pin "2") (pinfunction "2_2") (pintype "passive"))
      (node (ref "IC1") (pin "12") (pinfunction "AIN2_12") (pintype "passive"))
      (node (ref "U6") (pin "7") (pinfunction "Uout_7") (pintype "passive"))
    )
    (net (code "14") (name "/M2_PWM") (class "Default")
      (node (ref "J11") (pin "3") (pinfunction "3_3") (pintype "passive"))
      (node (ref "J11") (pin "4") (pinfunction "4_4") (pintype "passive"))
      (node (ref "P6") (pin "2") (pinfunction "2_2") (pintype "passive"))
    )
    (net (code "15") (name "/M3_Cur") (class "Default")
      (node (ref "C27") (pin "2") (pinfunction "2_2") (pintype "passive"))
      (node (ref "IC1") (pin "13") (pinfunction "AIN3_13") (pintype "passive"))
      (node (ref "U3") (pin "7") (pinfunction "Uout_7") (pintype "passive"))
    )
    (net (code "16") (name "/M3_PWM") (class "Default")
      (node (ref "J11") (pin "5") (pinfunction "5_5") (pintype "passive"))
      (node (ref "J11") (pin "6") (pinfunction "6_6") (pintype "passive"))
      (node (ref "P6") (pin "3") (pinfunction "3_3") (pintype "passive"))
    )
    (net (code "17") (name "/M4_Cur") (class "Default")
      (node (ref "C53") (pin "2") (pinfunction "2_2") (pintype "passive"))
      (node (ref "IC1") (pin "14") (pinfunction "AIN4_14") (pintype "passive"))
      (node (ref "U10") (pin "7") (pinfunction "Uout_7") (pintype "passive"))
    )
    (net (code "18") (name "/M4_PWM") (class "Default")
      (node (ref "J11") (pin "7") (pinfunction "7_7") (pintype "passive"))
      (node (ref "J11") (pin "8") (pinfunction "8_8") (pintype "passive"))
      (node (ref "P6") (pin "4") (pinfunction "4_4") (pintype "passive"))
    )
    (net (code "19") (name "/M5_Cur") (class "Default")
      (node (ref "C52") (pin "2") (pinfunction "2_2") (pintype "passive"))
      (node (ref "IC1") (pin "15") (pinfunction "AIN5_15") (pintype "passive"))
      (node (ref "U9") (pin "7") (pinfunction "Uout_7") (pintype "passive"))
    )
    (net (code "20") (name "/M5_PWM") (class "Default")
      (node (ref "J11") (pin "10") (pinfunction "10_10") (pintype "passive"))
      (node (ref "J11") (pin "9") (pinfunction "9_9") (pintype "passive"))
      (node (ref "P6") (pin "5") (pinfunction "5_5") (pintype "passive"))
    )
    (net (code "21") (name "/M6_Cur") (class "Default")
      (node (ref "C51") (pin "2") (pinfunction "2_2") (pintype "passive"))
      (node (ref "IC1") (pin "16") (pinfunction "AIN6_16") (pintype "passive"))
      (node (ref "U8") (pin "7") (pinfunction "Uout_7") (pintype "passive"))
    )
    (net (code "22") (name "/M6_PWM") (class "Default")
      (node (ref "J11") (pin "11") (pinfunction "11_11") (pintype "passive"))
      (node (ref "J11") (pin "12") (pinfunction "12_12") (pintype "passive"))
      (node (ref "P6") (pin "6") (pinfunction "6_6") (pintype "passive"))
    )
    (net (code "23") (name "/M_I2C_SCL") (class "Default")
      (node (ref "P4") (pin "3") (pinfunction "3_3") (pintype "passive"))
      (node (ref "X4") (pin "A2") (pinfunction "A2_A2") (pintype "passive"))
    )
    (net (code "24") (name "/M_I2C_SDA") (class "Default")
      (node (ref "P4") (pin "1") (pinfunction "1_1") (pintype "passive"))
      (node (ref "X4") (pin "A1") (pinfunction "A1_A1") (pintype "passive"))
    )
    (net (code "25") (name "/NRST") (class "Default")
      (node (ref "P2") (pin "5") (pinfunction "5_5") (pintype "passive"))
    )
    (net (code "26") (name "/RPI_UART_RX") (class "Default")
      (node (ref "P1") (pin "10") (pinfunction "10_10") (pintype "passive"))
    )
    (net (code "27") (name "/RPI_UART_TX") (class "Default")
      (node (ref "P1") (pin "8") (pinfunction "8_8") (pintype "passive"))
    )
    (net (code "28") (name "/S1_PWM") (class "Default")
      (node (ref "P6") (pin "7") (pinfunction "7_7") (pintype "passive"))
    )
    (net (code "29") (name "/S2_PWM") (class "Default")
      (node (ref "P6") (pin "8") (pinfunction "8_8") (pintype "passive"))
    )
    (net (code "30") (name "/S3_PWM") (class "Default")
      (node (ref "P5") (pin "1") (pinfunction "1_1") (pintype "passive"))
    )
    (net (code "31") (name "/S4_PWM") (class "Default")
      (node (ref "P5") (pin "3") (pinfunction "3_3") (pintype "passive"))
    )
    (net (code "32") (name "/S5_PWM") (class "Default")
      (node (ref "P5") (pin "5") (pinfunction "5_5") (pintype "passive"))
    )
    (net (code "33") (name "/S6_PWM") (class "Default")
      (node (ref "P5") (pin "7") (pinfunction "7_7") (pintype "passive"))
    )
    (net (code "34") (name "/S7_PWM") (class "Default")
      (node (ref "P5") (pin "2") (pinfunction "2_2") (pintype "passive"))
    )
    (net (code "35") (name "/S8_PWM") (class "Default")
      (node (ref "P5") (pin "4") (pinfunction "4_4") (pintype "passive"))
    )
    (net (code "36") (name "/S9_PWM") (class "Default")
      (node (ref "P5") (pin "6") (pinfunction "6_6") (pintype "passive"))
    )
    (net (code "37") (name "/SSPI1_CS1") (class "Default")
      (node (ref "P4") (pin "4") (pinfunction "4_4") (pintype "passive"))
      (node (ref "X4") (pin "A7") (pinfunction "A7_A7") (pintype "passive"))
    )
    (net (code "38") (name "/SSPI1_CS2") (class "Default")
      (node (ref "P4") (pin "6") (pinfunction "6_6") (pintype "passive"))
      (node (ref "X4") (pin "A8") (pinfunction "A8_A8") (pintype "passive"))
    )
    (net (code "39") (name "/SSPI1_CS3") (class "Default")
      (node (ref "P4") (pin "8") (pinfunction "8_8") (pintype "passive"))
      (node (ref "X4") (pin "A9") (pinfunction "A9_A9") (pintype "passive"))
    )
    (net (code "40") (name "/SSPI1_CS4") (class "Default")
      (node (ref "X4") (pin "B5") (pinfunction "B5_B5") (pintype "passive"))
    )
    (net (code "41") (name "/SSPI1_MISO") (class "Default")
      (node (ref "P4") (pin "7") (pinfunction "7_7") (pintype "passive"))
      (node (ref "X4") (pin "A4") (pinfunction "A4_A4") (pintype "passive"))
    )
    (net (code "42") (name "/SSPI1_MOSI") (class "Default")
      (node (ref "P4") (pin "5") (pinfunction "5_5") (pintype "passive"))
      (node (ref "X4") (pin "A3") (pinfunction "A3_A3") (pintype "passive"))
    )
    (net (code "43") (name "/SSPI1_SCK") (class "Default")
      (node (ref "P4") (pin "2") (pinfunction "2_2") (pintype "passive"))
      (node (ref "X4") (pin "A5") (pinfunction "A5_A5") (pintype "passive"))
    )
    (net (code "44") (name "/SSPI2_CS_Current") (class "Default")
      (node (ref "P5") (pin "8") (pinfunction "8_8") (pintype "passive"))
    )
    (net (code "45") (name "/SSPI2_CS_Current_Motors") (class "Default")
      (node (ref "IC1") (pin "4") (pinfunction "~{CS}_4") (pintype "passive"))
    )
    (net (code "46") (name "/SSPI2_MISO") (class "Default")
      (node (ref "IC1") (pin "27") (pinfunction "DOUT/~{RDY}_27") (pintype "passive"))
    )
    (net (code "47") (name "/SSPI2_MOSI") (class "Default")
      (node (ref "IC1") (pin "28") (pinfunction "DIN_28") (pintype "passive"))
    )
    (net (code "48") (name "/SSPI2_SCK") (class "Default")
      (node (ref "IC1") (pin "3") (pinfunction "SCLK_3") (pintype "passive"))
    )
    (net (code "49") (name "/SWCLK") (class "Default")
      (node (ref "P2") (pin "3") (pinfunction "3_3") (pintype "passive"))
    )
    (net (code "50") (name "/SWDIO") (class "Default")
      (node (ref "P2") (pin "1") (pinfunction "1_1") (pintype "passive"))
    )
    (net (code "51") (name "GND") (class "Default")
      (node (ref "C1") (pin "1") (pinfunction "1_1") (pintype "passive"))
      (node (ref "C12") (pin "1") (pinfunction "1_1") (pintype "passive"))
      (node (ref "C13") (pin "2") (pinfunction "2_2") (pintype "passive"))
      (node (ref "C2") (pin "1") (pinfunction "1_1") (pintype "passive"))
      (node (ref "C21") (pin "2") (pinfunction "N_2") (pintype "passive"))
      (node (ref "C22") (pin "2") (pinfunction "N_2") (pintype "passive"))
      (node (ref "C23") (pin "2") (pinfunction "N_2") (pintype "passive"))
      (node (ref "C24") (pin "2") (pinfunction "N_2") (pintype "passive"))
      (node (ref "C25") (pin "1") (pinfunction "1_1") (pintype "passive"))
      (node (ref "C26") (pin "1") (pinfunction "1_1") (pintype "passive"))
      (node (ref "C27") (pin "1") (pinfunction "1_1") (pintype "passive"))
      (node (ref "C28") (pin "1") (pinfunction "1_1") (pintype "passive"))
      (node (ref "C3") (pin "1") (pinfunction "1_1") (pintype "passive"))
      (node (ref "C39") (pin "1") (pinfunction "1_1") (pintype "passive"))
      (node (ref "C4") (pin "1") (pinfunction "1_1") (pintype "passive"))
      (node (ref "C40") (pin "1") (pinfunction "1_1") (pintype "passive"))
      (node (ref "C41") (pin "1") (pinfunction "1_1") (pintype "passive"))
      (node (ref "C42") (pin "1") (pinfunction "1_1") (pintype "passive"))
      (node (ref "C43") (pin "1") (pinfunction "1_1") (pintype "passive"))
      (node (ref "C44") (pin "1") (pinfunction "1_1") (pintype "passive"))
      (node (ref "C48") (pin "1") (pinfunction "1_1") (pintype "passive"))
      (node (ref "C49") (pin "1") (pinfunction "1_1") (pintype "passive"))
      (node (ref "C5") (pin "1") (pinfunction "1_1") (pintype "passive"))
      (node (ref "C50") (pin "1") (pinfunction "1_1") (pintype "passive"))
      (node (ref "C51") (pin "1") (pinfunction "1_1") (pintype "passive"))
      (node (ref "C52") (pin "1") (pinfunction "1_1") (pintype "passive"))
      (node (ref "C53") (pin "1") (pinfunction "1_1") (pintype "passive"))
      (node (ref "C54") (pin "1") (pinfunction "1_1") (pintype "passive"))
      (node (ref "C55") (pin "1") (pinfunction "1_1") (pintype "passive"))
      (node (ref "C56") (pin "1") (pinfunction "1_1") (pintype "passive"))
      (node (ref "C6") (pin "1") (pinfunction "1_1") (pintype "passive"))
      (node (ref "C7") (pin "1") (pinfunction "1_1") (pintype "passive"))
      (node (ref "C8") (pin "1") (pinfunction "1_1") (pintype "passive"))
      (node (ref "D1") (pin "2") (pinfunction "K_2") (pintype "passive"))
      (node (ref "D11") (pin "1") (pinfunction "1_1") (pintype "passive"))
      (node (ref "D12") (pin "1") (pinfunction "1_1") (pintype "passive"))
      (node (ref "D2") (pin "1") (pinfunction "K_1") (pintype "passive"))
      (node (ref "D3") (pin "1") (pinfunction "K_1") (pintype "passive"))
      (node (ref "D4") (pin "2") (pinfunction "K_2") (pintype "passive"))
      (node (ref "D5") (pin "2") (pinfunction "K_2") (pintype "passive"))
      (node (ref "D6") (pin "2") (pinfunction "K_2") (pintype "passive"))
      (node (ref "D9") (pin "2") (pinfunction "-_2") (pintype "passive"))
      (node (ref "IC1") (pin "10") (pinfunction "AINCOM_10") (pintype "passive"))
      (node (ref "IC1") (pin "20") (pinfunction "REFIN1(-)_20") (pintype "passive"))
      (node (ref "IC1") (pin "21") (pinfunction "BPDSW_21") (pintype "passive"))
      (node (ref "IC1") (pin "22") (pinfunction "AGND_22") (pintype "passive"))
      (node (ref "IC1") (pin "23") (pinfunction "DGND_23") (pintype "passive"))
      (node (ref "J1") (pin "5") (pinfunction "3.1_5") (pintype "passive"))
      (node (ref "J1") (pin "6") (pinfunction "3.2_6") (pintype "passive"))
      (node (ref "J1") (pin "7") (pinfunction "4.1_7") (pintype "passive"))
      (node (ref "J1") (pin "8") (pinfunction "4.2_8") (pintype "passive"))
      (node (ref "J10") (pin "A3") (pinfunction "A3_A3") (pintype "passive"))
      (node (ref "J10") (pin "A4") (pinfunction "A4_A4") (pintype "passive"))
      (node (ref "J10") (pin "B3") (pinfunction "B3_B3") (pintype "passive"))
      (node (ref "J10") (pin "B4") (pinfunction "B4_B4") (pintype "passive"))
      (node (ref "J12") (pin "1") (pinfunction "1_1") (pintype "passive"))
      (node (ref "J12") (pin "10") (pinfunction "10_10") (pintype "passive"))
      (node (ref "J12") (pin "11") (pinfunction "11_11") (pintype "passive"))
      (node (ref "J12") (pin "12") (pinfunction "12_12") (pintype "passive"))
      (node (ref "J12") (pin "13") (pinfunction "13_13") (pintype "passive"))
      (node (ref "J12") (pin "14") (pinfunction "14_14") (pintype "passive"))
      (node (ref "J12") (pin "15") (pinfunction "15_15") (pintype "passive"))
      (node (ref "J12") (pin "16") (pinfunction "16_16") (pintype "passive"))
      (node (ref "J12") (pin "17") (pinfunction "17_17") (pintype "passive"))
      (node (ref "J12") (pin "18") (pinfunction "18_18") (pintype "passive"))
      (node (ref "J12") (pin "2") (pinfunction "2_2") (pintype "passive"))
      (node (ref "J12") (pin "3") (pinfunction "3_3") (pintype "passive"))
      (node (ref "J12") (pin "4") (pinfunction "4_4") (pintype "passive"))
      (node (ref "J12") (pin "5") (pinfunction "5_5") (pintype "passive"))
      (node (ref "J12") (pin "6") (pinfunction "6_6") (pintype "passive"))
      (node (ref "J12") (pin "7") (pinfunction "7_7") (pintype "passive"))
      (node (ref "J12") (pin "8") (pinfunction "8_8") (pintype "passive"))
      (node (ref "J12") (pin "9") (pinfunction "9_9") (pintype "passive"))
      (node (ref "J13") (pin "A3") (pinfunction "A3_A3") (pintype "passive"))
      (node (ref "J13") (pin "A4") (pinfunction "A4_A4") (pintype "passive"))
      (node (ref "J13") (pin "B3") (pinfunction "B3_B3") (pintype "passive"))
      (node (ref "J13") (pin "B4") (pinfunction "B4_B4") (pintype "passive"))
      (node (ref "J14") (pin "A3") (pinfunction "A3_A3") (pintype "passive"))
      (node (ref "J14") (pin "A4") (pinfunction "A4_A4") (pintype "passive"))
      (node (ref "J14") (pin "B3") (pinfunction "B3_B3") (pintype "passive"))
      (node (ref "J14") (pin "B4") (pinfunction "B4_B4") (pintype "passive"))
      (node (ref "J8") (pin "1") (pinfunction "1.1_1") (pintype "passive"))
      (node (ref "J8") (pin "10") (pinfunction "5.2_10") (pintype "passive"))
      (node (ref "J8") (pin "11") (pinfunction "6.1_11") (pintype "passive"))
      (node (ref "J8") (pin "12") (pinfunction "6.2_12") (pintype "passive"))
      (node (ref "J8") (pin "13") (pinfunction "7.1_13") (pintype "passive"))
      (node (ref "J8") (pin "14") (pinfunction "7.2_14") (pintype "passive"))
      (node (ref "J8") (pin "15") (pinfunction "8.1_15") (pintype "passive"))
      (node (ref "J8") (pin "16") (pinfunction "8.2_16") (pintype "passive"))
      (node (ref "J8") (pin "2") (pinfunction "1.2_2") (pintype "passive"))
      (node (ref "J8") (pin "3") (pinfunction "2.1_3") (pintype "passive"))
      (node (ref "J8") (pin "4") (pinfunction "2.2_4") (pintype "passive"))
      (node (ref "J8") (pin "5") (pinfunction "3.1_5") (pintype "passive"))
      (node (ref "J8") (pin "6") (pinfunction "3.2_6") (pintype "passive"))
      (node (ref "J8") (pin "7") (pinfunction "4.1_7") (pintype "passive"))
      (node (ref "J8") (pin "8") (pinfunction "4.2_8") (pintype "passive"))
      (node (ref "J8") (pin "9") (pinfunction "5.1_9") (pintype "passive"))
      (node (ref "P1") (pin "14") (pinfunction "14_14") (pintype "passive"))
      (node (ref "P1") (pin "6") (pinfunction "6_6") (pintype "passive"))
      (node (ref "P2") (pin "6") (pinfunction "6_6") (pintype "passive"))
      (node (ref "P4") (pin "10") (pinfunction "10_10") (pintype "passive"))
      (node (ref "P4") (pin "9") (pinfunction "9_9") (pintype "passive"))
      (node (ref "P5") (pin "10") (pinfunction "10_10") (pintype "passive"))
      (node (ref "P5") (pin "9") (pinfunction "9_9") (pintype "passive"))
      (node (ref "P6") (pin "10") (pinfunction "10_10") (pintype "passive"))
      (node (ref "P6") (pin "9") (pinfunction "9_9") (pintype "passive"))
      (node (ref "PS1") (pin "2") (pinfunction "GND_2") (pintype "passive"))
      (node (ref "PS2") (pin "2") (pinfunction "GND_2") (pintype "passive"))
      (node (ref "PS3") (pin "2") (pinfunction "-VIN_2") (pintype "passive"))
      (node (ref "PS3") (pin "5") (pinfunction "-VOUT_5") (pintype "passive"))
      (node (ref "R16") (pin "1") (pinfunction "1_1") (pintype "passive"))
      (node (ref "R17") (pin "1") (pinfunction "1_1") (pintype "passive"))
      (node (ref "U10") (pin "5") (pinfunction "GND_5") (pintype "passive"))
      (node (ref "U3") (pin "5") (pinfunction "GND_5") (pintype "passive"))
      (node (ref "U6") (pin "5") (pinfunction "GND_5") (pintype "passive"))
      (node (ref "U7") (pin "5") (pinfunction "GND_5") (pintype "passive"))
      (node (ref "U8") (pin "5") (pinfunction "GND_5") (pintype "passive"))
      (node (ref "U9") (pin "5") (pinfunction "GND_5") (pintype "passive"))
      (node (ref "X4") (pin "A13") (pinfunction "A13_A13") (pintype "passive"))
      (node (ref "X4") (pin "A14") (pinfunction "A14_A14") (pintype "passive"))
      (node (ref "X4") (pin "A15") (pinfunction "A15_A15") (pintype "passive"))
      (node (ref "X4") (pin "A16") (pinfunction "A16_A16") (pintype "passive"))
      (node (ref "X4") (pin "B13") (pinfunction "B13_B13") (pintype "passive"))
      (node (ref "X4") (pin "B14") (pinfunction "B14_B14") (pintype "passive"))
      (node (ref "X4") (pin "B15") (pinfunction "B15_B15") (pintype "passive"))
      (node (ref "X4") (pin "B16") (pinfunction "B16_B16") (pintype "passive"))
      (node (ref "X4") (pin "B3") (pinfunction "B3_B3") (pintype "passive"))
      (node (ref "X4") (pin "B4") (pinfunction "B4_B4") (pintype "passive"))
      (node (ref "X4") (pin "C13") (pinfunction "C13_C13") (pintype "passive"))
      (node (ref "X4") (pin "C14") (pinfunction "C14_C14") (pintype "passive"))
      (node (ref "X4") (pin "C15") (pinfunction "C15_C15") (pintype "passive"))
      (node (ref "X4") (pin "C16") (pinfunction "C16_C16") (pintype "passive"))
      (node (ref "X4") (pin "MH1") (pinfunction "MH1_MH1") (pintype "passive"))
      (node (ref "X4") (pin "MH2") (pinfunction "MH2_MH2") (pintype "passive"))
    )
    (net (code "52") (name "Net-(C23-P)") (class "Default")
      (node (ref "C23") (pin "1") (pinfunction "P_1") (pintype "passive"))
      (node (ref "J13") (pin "A1") (pinfunction "A1_A1") (pintype "passive"))
      (node (ref "J13") (pin "B1") (pinfunction "B1_B1") (pintype "passive"))
      (node (ref "R11") (pin "2") (pinfunction "2_2") (pintype "passive"))
      (node (ref "R8") (pin "2") (pinfunction "2_2") (pintype "passive"))
      (node (ref "U3") (pin "1") (pinfunction "IP+_1") (pintype "passive"))
      (node (ref "U3") (pin "2") (pintype "passive"))
      (node (ref "U6") (pin "1") (pinfunction "IP+_1") (pintype "passive"))
      (node (ref "U6") (pin "2") (pintype "passive"))
      (node (ref "U7") (pin "1") (pinfunction "IP+_1") (pintype "passive"))
      (node (ref "U7") (pin "2") (pintype "passive"))
    )
    (net (code "53") (name "Net-(C24-P)") (class "Default")
      (node (ref "C24") (pin "1") (pinfunction "P_1") (pintype "passive"))
      (node (ref "J13") (pin "A2") (pinfunction "A2_A2") (pintype "passive"))
      (node (ref "J13") (pin "B2") (pinfunction "B2_B2") (pintype "passive"))
      (node (ref "R12") (pin "2") (pinfunction "2_2") (pintype "passive"))
      (node (ref "R13") (pin "2") (pinfunction "2_2") (pintype "passive"))
      (node (ref "U10") (pin "1") (pinfunction "IP+_1") (pintype "passive"))
      (node (ref "U10") (pin "2") (pintype "passive"))
      (node (ref "U8") (pin "1") (pinfunction "IP+_1") (pintype "passive"))
      (node (ref "U8") (pin "2") (pintype "passive"))
      (node (ref "U9") (pin "1") (pinfunction "IP+_1") (pintype "passive"))
      (node (ref "U9") (pin "2") (pintype "passive"))
    )
    (net (code "54") (name "Net-(D1-A)") (class "Default")
      (node (ref "D1") (pin "1") (pinfunction "A_1") (pintype "passive"))
      (node (ref "R1") (pin "1") (pinfunction "1_1") (pintype "passive"))
    )
    (net (code "55") (name "Net-(D2-A)") (class "Default")
      (node (ref "D2") (pin "2") (pinfunction "A_2") (pintype "passive"))
      (node (ref "R8") (pin "1") (pinfunction "1_1") (pintype "passive"))
    )
    (net (code "56") (name "Net-(D3-A)") (class "Default")
      (node (ref "D3") (pin "2") (pinfunction "A_2") (pintype "passive"))
      (node (ref "R12") (pin "1") (pinfunction "1_1") (pintype "passive"))
    )
    (net (code "57") (name "Net-(D4-A)") (class "Default")
      (node (ref "D4") (pin "1") (pinfunction "A_1") (pintype "passive"))
      (node (ref "R2") (pin "1") (pinfunction "1_1") (pintype "passive"))
    )
    (net (code "58") (name "Net-(D5-A)") (class "Default")
      (node (ref "D5") (pin "1") (pinfunction "A_1") (pintype "passive"))
      (node (ref "R3") (pin "1") (pinfunction "1_1") (pintype "passive"))
    )
    (net (code "59") (name "Net-(D6-A)") (class "Default")
      (node (ref "D6") (pin "1") (pinfunction "A_1") (pintype "passive"))
      (node (ref "R9") (pin "1") (pinfunction "1_1") (pintype "passive"))
    )
    (net (code "60") (name "Net-(J5-1.1)") (class "Default")
      (node (ref "J5") (pin "1") (pinfunction "1.1_1") (pintype "passive"))
      (node (ref "J5") (pin "2") (pinfunction "1.2_2") (pintype "passive"))
      (node (ref "J5") (pin "3") (pinfunction "2.1_3") (pintype "passive"))
      (node (ref "J5") (pin "4") (pinfunction "2.2_4") (pintype "passive"))
    )
    (net (code "61") (name "Net-(J5-3.1)") (class "Default")
      (node (ref "J5") (pin "5") (pinfunction "3.1_5") (pintype "passive"))
      (node (ref "J5") (pin "6") (pinfunction "3.2_6") (pintype "passive"))
      (node (ref "U7") (pin "3") (pintype "passive"))
      (node (ref "U7") (pin "4") (pinfunction "IP-_4") (pintype "passive"))
    )
    (net (code "62") (name "Net-(J5-4.1)") (class "Default")
      (node (ref "J5") (pin "7") (pinfunction "4.1_7") (pintype "passive"))
      (node (ref "J5") (pin "8") (pinfunction "4.2_8") (pintype "passive"))
      (node (ref "U6") (pin "3") (pintype "passive"))
      (node (ref "U6") (pin "4") (pinfunction "IP-_4") (pintype "passive"))
    )
    (net (code "63") (name "Net-(J5-5.1)") (class "Default")
      (node (ref "J5") (pin "10") (pinfunction "5.2_10") (pintype "passive"))
      (node (ref "J5") (pin "9") (pinfunction "5.1_9") (pintype "passive"))
      (node (ref "U3") (pin "3") (pintype "passive"))
      (node (ref "U3") (pin "4") (pinfunction "IP-_4") (pintype "passive"))
    )
    (net (code "64") (name "Net-(J5-6.1)") (class "Default")
      (node (ref "J5") (pin "11") (pinfunction "6.1_11") (pintype "passive"))
      (node (ref "J5") (pin "12") (pinfunction "6.2_12") (pintype "passive"))
      (node (ref "U10") (pin "3") (pintype "passive"))
      (node (ref "U10") (pin "4") (pinfunction "IP-_4") (pintype "passive"))
    )
    (net (code "65") (name "Net-(J5-7.1)") (class "Default")
      (node (ref "J5") (pin "13") (pinfunction "7.1_13") (pintype "passive"))
      (node (ref "J5") (pin "14") (pinfunction "7.2_14") (pintype "passive"))
      (node (ref "U9") (pin "3") (pintype "passive"))
      (node (ref "U9") (pin "4") (pinfunction "IP-_4") (pintype "passive"))
    )
    (net (code "66") (name "Net-(J5-8.1)") (class "Default")
      (node (ref "J5") (pin "15") (pinfunction "8.1_15") (pintype "passive"))
      (node (ref "J5") (pin "16") (pinfunction "8.2_16") (pintype "passive"))
      (node (ref "U8") (pin "3") (pintype "passive"))
      (node (ref "U8") (pin "4") (pinfunction "IP-_4") (pintype "passive"))
    )
    (net (code "67") (name "Net-(U3-Uref)") (class "Default")
      (node (ref "C26") (pin "2") (pinfunction "2_2") (pintype "passive"))
      (node (ref "U3") (pin "6") (pinfunction "Uref_6") (pintype "passive"))
    )
    (net (code "68") (name "Net-(U6-Uref)") (class "Default")
      (node (ref "C39") (pin "2") (pinfunction "2_2") (pintype "passive"))
      (node (ref "U6") (pin "6") (pinfunction "Uref_6") (pintype "passive"))
    )
    (net (code "69") (name "Net-(U7-Uref)") (class "Default")
      (node (ref "C40") (pin "2") (pinfunction "2_2") (pintype "passive"))
      (node (ref "U7") (pin "6") (pinfunction "Uref_6") (pintype "passive"))
    )
    (net (code "70") (name "Net-(U8-Uref)") (class "Default")
      (node (ref "C48") (pin "2") (pinfunction "2_2") (pintype "passive"))
      (node (ref "U8") (pin "6") (pinfunction "Uref_6") (pintype "passive"))
    )
    (net (code "71") (name "Net-(U9-Uref)") (class "Default")
      (node (ref "C49") (pin "2") (pinfunction "2_2") (pintype "passive"))
      (node (ref "U9") (pin "6") (pinfunction "Uref_6") (pintype "passive"))
    )
    (net (code "72") (name "Net-(U10-Uref)") (class "Default")
      (node (ref "C50") (pin "2") (pinfunction "2_2") (pintype "passive"))
      (node (ref "U10") (pin "6") (pinfunction "Uref_6") (pintype "passive"))
    )
    (net (code "73") (name "unconnected-(D9-NC-Pad3)") (class "Default")
      (node (ref "D9") (pin "3") (pinfunction "NC_3") (pintype "passive"))
    )
    (net (code "74") (name "unconnected-(IC1-AIN7-Pad17)") (class "Default")
      (node (ref "IC1") (pin "17") (pinfunction "AIN7_17") (pintype "passive"))
    )
    (net (code "75") (name "unconnected-(IC1-AIN8-Pad18)") (class "Default")
      (node (ref "IC1") (pin "18") (pinfunction "AIN8_18") (pintype "passive"))
    )
    (net (code "76") (name "unconnected-(IC1-AVDD-Pad24)") (class "Default")
      (node (ref "IC1") (pin "24") (pinfunction "AVDD_24") (pintype "passive"))
    )
    (net (code "77") (name "unconnected-(IC1-MCLK1-Pad1)") (class "Default")
      (node (ref "IC1") (pin "1") (pinfunction "MCLK1_1") (pintype "passive+no_connect"))
    )
    (net (code "78") (name "unconnected-(IC1-MCLK2-Pad2)") (class "Default")
      (node (ref "IC1") (pin "2") (pinfunction "MCLK2_2") (pintype "passive+no_connect"))
    )
    (net (code "79") (name "unconnected-(IC1-NC-Pad9)") (class "Default")
      (node (ref "IC1") (pin "9") (pinfunction "NC_9") (pintype "passive"))
    )
    (net (code "80") (name "unconnected-(IC1-P0{slash}REFIN2(-)-Pad8)") (class "Default")
      (node (ref "IC1") (pin "8") (pinfunction "P0/REFIN2(-)_8") (pintype "passive"))
    )
    (net (code "81") (name "unconnected-(IC1-P1{slash}REFIN2(+)-Pad7)") (class "Default")
      (node (ref "IC1") (pin "7") (pinfunction "P1/REFIN2(+)_7") (pintype "passive"))
    )
    (net (code "82") (name "unconnected-(IC1-P2-Pad6)") (class "Default")
      (node (ref "IC1") (pin "6") (pinfunction "P2_6") (pintype "passive"))
    )
    (net (code "83") (name "unconnected-(IC1-P3-Pad5)") (class "Default")
      (node (ref "IC1") (pin "5") (pinfunction "P3_5") (pintype "passive"))
    )
    (net (code "84") (name "unconnected-(IC1-~{SYNC}-Pad26)") (class "Default")
      (node (ref "IC1") (pin "26") (pinfunction "~{SYNC}_26") (pintype "passive+no_connect"))
    )
    (net (code "85") (name "unconnected-(P1-Pad1)") (class "Default")
      (node (ref "P1") (pin "1") (pinfunction "1_1") (pintype "passive"))
    )
    (net (code "86") (name "unconnected-(P1-Pad3)") (class "Default")
      (node (ref "P1") (pin "3") (pinfunction "3_3") (pintype "passive"))
    )
    (net (code "87") (name "unconnected-(P1-Pad5)") (class "Default")
      (node (ref "P1") (pin "5") (pinfunction "5_5") (pintype "passive"))
    )
    (net (code "88") (name "unconnected-(P1-Pad7)") (class "Default")
      (node (ref "P1") (pin "7") (pinfunction "7_7") (pintype "passive"))
    )
    (net (code "89") (name "unconnected-(P1-Pad9)") (class "Default")
      (node (ref "P1") (pin "9") (pinfunction "9_9") (pintype "passive"))
    )
    (net (code "90") (name "unconnected-(P1-Pad11)") (class "Default")
      (node (ref "P1") (pin "11") (pinfunction "11_11") (pintype "passive"))
    )
    (net (code "91") (name "unconnected-(P1-Pad12)") (class "Default")
      (node (ref "P1") (pin "12") (pinfunction "12_12") (pintype "passive"))
    )
    (net (code "92") (name "unconnected-(P1-Pad13)") (class "Default")
      (node (ref "P1") (pin "13") (pinfunction "13_13") (pintype "passive"))
    )
    (net (code "93") (name "unconnected-(P1-Pad15)") (class "Default")
      (node (ref "P1") (pin "15") (pinfunction "15_15") (pintype "passive"))
    )
    (net (code "94") (name "unconnected-(P1-Pad16)") (class "Default")
      (node (ref "P1") (pin "16") (pinfunction "16_16") (pintype "passive"))
    )
    (net (code "95") (name "unconnected-(P1-Pad17)") (class "Default")
      (node (ref "P1") (pin "17") (pinfunction "17_17") (pintype "passive"))
    )
    (net (code "96") (name "unconnected-(P1-Pad18)") (class "Default")
      (node (ref "P1") (pin "18") (pinfunction "18_18") (pintype "passive"))
    )
    (net (code "97") (name "unconnected-(P1-Pad19)") (class "Default")
      (node (ref "P1") (pin "19") (pinfunction "19_19") (pintype "passive"))
    )
    (net (code "98") (name "unconnected-(P1-Pad20)") (class "Default")
      (node (ref "P1") (pin "20") (pinfunction "20_20") (pintype "passive"))
    )
    (net (code "99") (name "unconnected-(P1-Pad21)") (class "Default")
      (node (ref "P1") (pin "21") (pinfunction "21_21") (pintype "passive"))
    )
    (net (code "100") (name "unconnected-(P1-Pad22)") (class "Default")
      (node (ref "P1") (pin "22") (pinfunction "22_22") (pintype "passive"))
    )
    (net (code "101") (name "unconnected-(P1-Pad23)") (class "Default")
      (node (ref "P1") (pin "23") (pinfunction "23_23") (pintype "passive"))
    )
    (net (code "102") (name "unconnected-(P1-Pad24)") (class "Default")
      (node (ref "P1") (pin "24") (pinfunction "24_24") (pintype "passive"))
    )
    (net (code "103") (name "unconnected-(P1-Pad25)") (class "Default")
      (node (ref "P1") (pin "25") (pinfunction "25_25") (pintype "passive"))
    )
    (net (code "104") (name "unconnected-(P1-Pad26)") (class "Default")
      (node (ref "P1") (pin "26") (pinfunction "26_26") (pintype "passive"))
    )
    (net (code "105") (name "unconnected-(P1-Pad27)") (class "Default")
      (node (ref "P1") (pin "27") (pinfunction "27_27") (pintype "passive"))
    )
    (net (code "106") (name "unconnected-(P1-Pad28)") (class "Default")
      (node (ref "P1") (pin "28") (pinfunction "28_28") (pintype "passive"))
    )
    (net (code "107") (name "unconnected-(P1-Pad29)") (class "Default")
      (node (ref "P1") (pin "29") (pinfunction "29_29") (pintype "passive"))
    )
    (net (code "108") (name "unconnected-(P1-Pad30)") (class "Default")
      (node (ref "P1") (pin "30") (pinfunction "30_30") (pintype "passive"))
    )
    (net (code "109") (name "unconnected-(P1-Pad31)") (class "Default")
      (node (ref "P1") (pin "31") (pinfunction "31_31") (pintype "passive"))
    )
    (net (code "110") (name "unconnected-(P1-Pad32)") (class "Default")
      (node (ref "P1") (pin "32") (pinfunction "32_32") (pintype "passive"))
    )
    (net (code "111") (name "unconnected-(P1-Pad33)") (class "Default")
      (node (ref "P1") (pin "33") (pinfunction "33_33") (pintype "passive"))
    )
    (net (code "112") (name "unconnected-(P1-Pad34)") (class "Default")
      (node (ref "P1") (pin "34") (pinfunction "34_34") (pintype "passive"))
    )
    (net (code "113") (name "unconnected-(P1-Pad35)") (class "Default")
      (node (ref "P1") (pin "35") (pinfunction "35_35") (pintype "passive"))
    )
    (net (code "114") (name "unconnected-(P1-Pad36)") (class "Default")
      (node (ref "P1") (pin "36") (pinfunction "36_36") (pintype "passive"))
    )
    (net (code "115") (name "unconnected-(P1-Pad37)") (class "Default")
      (node (ref "P1") (pin "37") (pinfunction "37_37") (pintype "passive"))
    )
    (net (code "116") (name "unconnected-(P1-Pad38)") (class "Default")
      (node (ref "P1") (pin "38") (pinfunction "38_38") (pintype "passive"))
    )
    (net (code "117") (name "unconnected-(P1-Pad39)") (class "Default")
      (node (ref "P1") (pin "39") (pinfunction "39_39") (pintype "passive"))
    )
    (net (code "118") (name "unconnected-(P1-Pad40)") (class "Default")
      (node (ref "P1") (pin "40") (pinfunction "40_40") (pintype "passive"))
    )
    (net (code "119") (name "unconnected-(P2-Pad4)") (class "Default")
      (node (ref "P2") (pin "4") (pinfunction "4_4") (pintype "passive+no_connect"))
    )
    (net (code "120") (name "unconnected-(PS3-REMOTE_ON{slash}OFF-Pad6)") (class "Default")
      (node (ref "PS3") (pin "6") (pinfunction "REMOTE_ON/OFF_6") (pintype "passive"))
    )
    (net (code "121") (name "unconnected-(PS3-TRIM-Pad4)") (class "Default")
      (node (ref "PS3") (pin "4") (pinfunction "TRIM_4") (pintype "passive"))
    )
    (net (code "122") (name "unconnected-(X4-PadA6)") (class "Default")
      (node (ref "X4") (pin "A6") (pinfunction "A6_A6") (pintype "passive"))
    )
    (net (code "123") (name "unconnected-(X4-PadB6)") (class "Default")
      (node (ref "X4") (pin "B6") (pinfunction "B6_B6") (pintype "passive"))
    )
    (net (code "124") (name "unconnected-(X4-PadB7)") (class "Default")
      (node (ref "X4") (pin "B7") (pinfunction "B7_B7") (pintype "passive"))
    )
    (net (code "125") (name "unconnected-(X4-PadB8)") (class "Default")
      (node (ref "X4") (pin "B8") (pinfunction "B8_B8") (pintype "passive"))
    )
    (net (code "126") (name "unconnected-(X4-PadB9)") (class "Default")
      (node (ref "X4") (pin "B9") (pinfunction "B9_B9") (pintype "passive"))
    )
    (net (code "127") (name "unconnected-(X4-PadC1)") (class "Default")
      (node (ref "X4") (pin "C1") (pinfunction "C1_C1") (pintype "passive"))
    )
    (net (code "128") (name "unconnected-(X4-PadC2)") (class "Default")
      (node (ref "X4") (pin "C2") (pinfunction "C2_C2") (pintype "passive"))
    )
    (net (code "129") (name "unconnected-(X4-PadC3)") (class "Default")
      (node (ref "X4") (pin "C3") (pinfunction "C3_C3") (pintype "passive"))
    )
    (net (code "130") (name "unconnected-(X4-PadC4)") (class "Default")
      (node (ref "X4") (pin "C4") (pinfunction "C4_C4") (pintype "passive"))
    )
    (net (code "131") (name "unconnected-(X4-PadC5)") (class "Default")
      (node (ref "X4") (pin "C5") (pinfunction "C5_C5") (pintype "passive"))
    )
    (net (code "132") (name "unconnected-(X4-PadC6)") (class "Default")
      (node (ref "X4") (pin "C6") (pinfunction "C6_C6") (pintype "passive"))
    )
    (net (code "133") (name "unconnected-(X4-PadC7)") (class "Default")
      (node (ref "X4") (pin "C7") (pinfunction "C7_C7") (pintype "passive"))
    )
    (net (code "134") (name "unconnected-(X4-PadC8)") (class "Default")
      (node (ref "X4") (pin "C8") (pinfunction "C8_C8") (pintype "passive"))
    )
    (net (code "135") (name "unconnected-(X4-PadC9)") (class "Default")
      (node (ref "X4") (pin "C9") (pinfunction "C9_C9") (pintype "passive"))
    )
  )
)
